# B156A.net
KiCad netlist of a schematic drawn in EAGLE
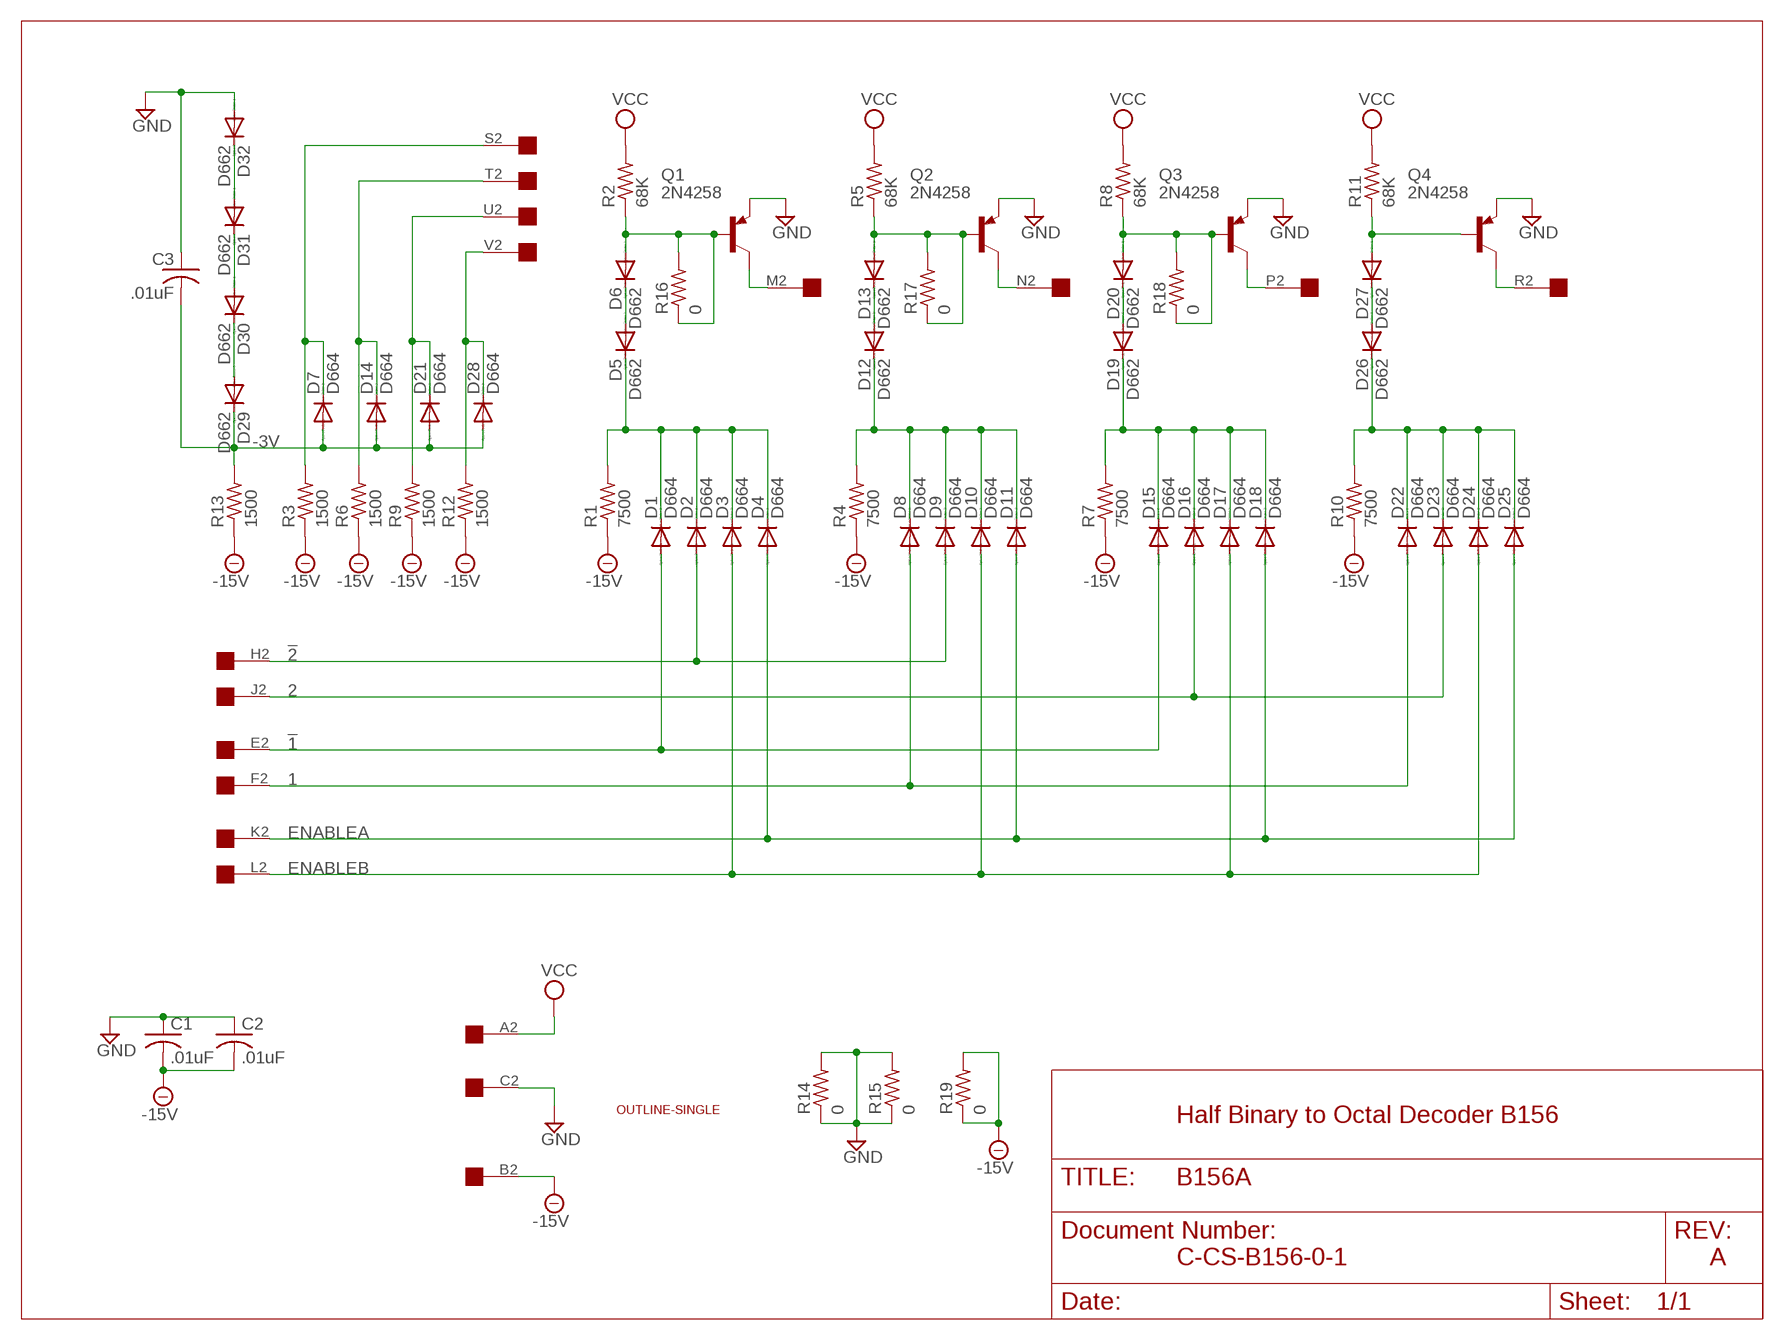
[diagram p0: schematic, sheet 1]

(export (version "E")
  (design (tool "Eeschema 10.0.6"))
  (components
    (comp (ref "C1")
      (value ".01uF")
      (footprint "eagle-import:C063-025X075")
      (libsource (lib "eagle-import") (part "C-US"))
    )
    (comp (ref "C2")
      (value ".01uF")
      (footprint "eagle-import:C063-025X075")
      (libsource (lib "eagle-import") (part "C-US"))
    )
    (comp (ref "C3")
      (value ".01uF")
      (footprint "eagle-import:C063-025X075")
      (libsource (lib "eagle-import") (part "C-US"))
    )
    (comp (ref "D1")
      (value "D664")
      (footprint "eagle-import:DO35-10")
      (libsource (lib "eagle-import") (part "DIODE-DO35-10"))
    )
    (comp (ref "D2")
      (value "D664")
      (footprint "eagle-import:DO35-10")
      (libsource (lib "eagle-import") (part "DIODE-DO35-10"))
    )
    (comp (ref "D3")
      (value "D664")
      (footprint "eagle-import:DO35-10")
      (libsource (lib "eagle-import") (part "DIODE-DO35-10"))
    )
    (comp (ref "D4")
      (value "D664")
      (footprint "eagle-import:DO35-10")
      (libsource (lib "eagle-import") (part "DIODE-DO35-10"))
    )
    (comp (ref "D5")
      (value "D662")
      (footprint "eagle-import:DO35-10")
      (libsource (lib "eagle-import") (part "DIODE-DO35-10"))
    )
    (comp (ref "D6")
      (value "D662")
      (footprint "eagle-import:DO35-10")
      (libsource (lib "eagle-import") (part "DIODE-DO35-10"))
    )
    (comp (ref "D7")
      (value "D664")
      (footprint "eagle-import:DO35-10")
      (libsource (lib "eagle-import") (part "DIODE-DO35-10"))
    )
    (comp (ref "D8")
      (value "D664")
      (footprint "eagle-import:DO35-10")
      (libsource (lib "eagle-import") (part "DIODE-DO35-10"))
    )
    (comp (ref "D9")
      (value "D664")
      (footprint "eagle-import:DO35-10")
      (libsource (lib "eagle-import") (part "DIODE-DO35-10"))
    )
    (comp (ref "D10")
      (value "D664")
      (footprint "eagle-import:DO35-10")
      (libsource (lib "eagle-import") (part "DIODE-DO35-10"))
    )
    (comp (ref "D11")
      (value "D664")
      (footprint "eagle-import:DO35-10")
      (libsource (lib "eagle-import") (part "DIODE-DO35-10"))
    )
    (comp (ref "D12")
      (value "D662")
      (footprint "eagle-import:DO35-10")
      (libsource (lib "eagle-import") (part "DIODE-DO35-10"))
    )
    (comp (ref "D13")
      (value "D662")
      (footprint "eagle-import:DO35-10")
      (libsource (lib "eagle-import") (part "DIODE-DO35-10"))
    )
    (comp (ref "D14")
      (value "D664")
      (footprint "eagle-import:DO35-10")
      (libsource (lib "eagle-import") (part "DIODE-DO35-10"))
    )
    (comp (ref "D15")
      (value "D664")
      (footprint "eagle-import:DO35-10")
      (libsource (lib "eagle-import") (part "DIODE-DO35-10"))
    )
    (comp (ref "D16")
      (value "D664")
      (footprint "eagle-import:DO35-10")
      (libsource (lib "eagle-import") (part "DIODE-DO35-10"))
    )
    (comp (ref "D17")
      (value "D664")
      (footprint "eagle-import:DO35-10")
      (libsource (lib "eagle-import") (part "DIODE-DO35-10"))
    )
    (comp (ref "D18")
      (value "D664")
      (footprint "eagle-import:DO35-10")
      (libsource (lib "eagle-import") (part "DIODE-DO35-10"))
    )
    (comp (ref "D19")
      (value "D662")
      (footprint "eagle-import:DO35-10")
      (libsource (lib "eagle-import") (part "DIODE-DO35-10"))
    )
    (comp (ref "D20")
      (value "D662")
      (footprint "eagle-import:DO35-10")
      (libsource (lib "eagle-import") (part "DIODE-DO35-10"))
    )
    (comp (ref "D21")
      (value "D664")
      (footprint "eagle-import:DO35-10")
      (libsource (lib "eagle-import") (part "DIODE-DO35-10"))
    )
    (comp (ref "D22")
      (value "D664")
      (footprint "eagle-import:DO35-10")
      (libsource (lib "eagle-import") (part "DIODE-DO35-10"))
    )
    (comp (ref "D23")
      (value "D664")
      (footprint "eagle-import:DO35-10")
      (libsource (lib "eagle-import") (part "DIODE-DO35-10"))
    )
    (comp (ref "D24")
      (value "D664")
      (footprint "eagle-import:DO35-10")
      (libsource (lib "eagle-import") (part "DIODE-DO35-10"))
    )
    (comp (ref "D25")
      (value "D664")
      (footprint "eagle-import:DO35-10")
      (libsource (lib "eagle-import") (part "DIODE-DO35-10"))
    )
    (comp (ref "D26")
      (value "D662")
      (footprint "eagle-import:DO35-10")
      (libsource (lib "eagle-import") (part "DIODE-DO35-10"))
    )
    (comp (ref "D27")
      (value "D662")
      (footprint "eagle-import:DO35-10")
      (libsource (lib "eagle-import") (part "DIODE-DO35-10"))
    )
    (comp (ref "D28")
      (value "D664")
      (footprint "eagle-import:DO35-10")
      (libsource (lib "eagle-import") (part "DIODE-DO35-10"))
    )
    (comp (ref "D29")
      (value "D662")
      (footprint "eagle-import:DO35-10")
      (libsource (lib "eagle-import") (part "DIODE-DO35-10"))
    )
    (comp (ref "D30")
      (value "D662")
      (footprint "eagle-import:DO35-10")
      (libsource (lib "eagle-import") (part "DIODE-DO35-10"))
    )
    (comp (ref "D31")
      (value "D662")
      (footprint "eagle-import:DO35-10")
      (libsource (lib "eagle-import") (part "DIODE-DO35-10"))
    )
    (comp (ref "D32")
      (value "D662")
      (footprint "eagle-import:DO35-10")
      (libsource (lib "eagle-import") (part "DIODE-DO35-10"))
    )
    (comp (ref "Q1")
      (value "2N4258")
      (footprint "eagle-import:TO5")
      (libsource (lib "eagle-import") (part "-PNP-TO5"))
    )
    (comp (ref "Q2")
      (value "2N4258")
      (footprint "eagle-import:TO5")
      (libsource (lib "eagle-import") (part "-PNP-TO5"))
    )
    (comp (ref "Q3")
      (value "2N4258")
      (footprint "eagle-import:TO5")
      (libsource (lib "eagle-import") (part "-PNP-TO5"))
    )
    (comp (ref "Q4")
      (value "2N4258")
      (footprint "eagle-import:TO5")
      (libsource (lib "eagle-import") (part "-PNP-TO5"))
    )
    (comp (ref "R1")
      (value "7500")
      (footprint "eagle-import:0207_10")
      (libsource (lib "eagle-import") (part "R-US_0207/10"))
    )
    (comp (ref "R2")
      (value "68K")
      (footprint "eagle-import:0207_10")
      (libsource (lib "eagle-import") (part "R-US_0207/10"))
    )
    (comp (ref "R3")
      (value "1500")
      (footprint "eagle-import:0207_10")
      (libsource (lib "eagle-import") (part "R-US_0207/10"))
    )
    (comp (ref "R4")
      (value "7500")
      (footprint "eagle-import:0207_10")
      (libsource (lib "eagle-import") (part "R-US_0207/10"))
    )
    (comp (ref "R5")
      (value "68K")
      (footprint "eagle-import:0207_10")
      (libsource (lib "eagle-import") (part "R-US_0207/10"))
    )
    (comp (ref "R6")
      (value "1500")
      (footprint "eagle-import:0207_10")
      (libsource (lib "eagle-import") (part "R-US_0207/10"))
    )
    (comp (ref "R7")
      (value "7500")
      (footprint "eagle-import:0207_10")
      (libsource (lib "eagle-import") (part "R-US_0207/10"))
    )
    (comp (ref "R8")
      (value "68K")
      (footprint "eagle-import:0207_10")
      (libsource (lib "eagle-import") (part "R-US_0207/10"))
    )
    (comp (ref "R9")
      (value "1500")
      (footprint "eagle-import:0207_10")
      (libsource (lib "eagle-import") (part "R-US_0207/10"))
    )
    (comp (ref "R10")
      (value "7500")
      (footprint "eagle-import:0207_10")
      (libsource (lib "eagle-import") (part "R-US_0207/10"))
    )
    (comp (ref "R11")
      (value "68K")
      (footprint "eagle-import:0207_10")
      (libsource (lib "eagle-import") (part "R-US_0207/10"))
    )
    (comp (ref "R12")
      (value "1500")
      (footprint "eagle-import:0207_10")
      (libsource (lib "eagle-import") (part "R-US_0207/10"))
    )
    (comp (ref "R13")
      (value "1500")
      (footprint "eagle-import:0207_10")
      (libsource (lib "eagle-import") (part "R-US_0207/10"))
    )
    (comp (ref "R14")
      (value "0")
      (footprint "eagle-import:0207_10")
      (libsource (lib "eagle-import") (part "R-US_0207/10"))
    )
    (comp (ref "R15")
      (value "0")
      (footprint "eagle-import:0207_10")
      (libsource (lib "eagle-import") (part "R-US_0207/10"))
    )
    (comp (ref "R16")
      (value "0")
      (footprint "eagle-import:0207_10")
      (libsource (lib "eagle-import") (part "R-US_0207/10"))
    )
    (comp (ref "R17")
      (value "0")
      (footprint "eagle-import:0207_10")
      (libsource (lib "eagle-import") (part "R-US_0207/10"))
    )
    (comp (ref "R18")
      (value "0")
      (footprint "eagle-import:0207_10")
      (libsource (lib "eagle-import") (part "R-US_0207/10"))
    )
    (comp (ref "R19")
      (value "0")
      (footprint "eagle-import:0207_10")
      (libsource (lib "eagle-import") (part "R-US_0207/10"))
    )
    (comp (ref "U$1")
      (value "OUTLINE-SINGLE")
      (footprint "eagle-import:SINGLE")
      (libsource (lib "eagle-import") (part "OUTLINE-SINGLE"))
    )
    (comp (ref "U$2")
      (value "EDGE-1")
      (footprint "eagle-import:EDGE-CON1")
      (libsource (lib "eagle-import") (part "EDGE-1"))
    )
  )
  (nets
    (net (code "1") (name "-15V") (class "Default")
      (node (ref "C1") (pin "2") (pinfunction "2_2") (pintype "passive"))
      (node (ref "C2") (pin "2") (pinfunction "2_2") (pintype "passive"))
      (node (ref "R1") (pin "1") (pinfunction "1_1") (pintype "passive"))
      (node (ref "R10") (pin "1") (pinfunction "1_1") (pintype "passive"))
      (node (ref "R12") (pin "1") (pinfunction "1_1") (pintype "passive"))
      (node (ref "R13") (pin "1") (pinfunction "1_1") (pintype "passive"))
      (node (ref "R19") (pin "1") (pinfunction "1_1") (pintype "passive"))
      (node (ref "R19") (pin "2") (pinfunction "2_2") (pintype "passive"))
      (node (ref "R3") (pin "1") (pinfunction "1_1") (pintype "passive"))
      (node (ref "R4") (pin "1") (pinfunction "1_1") (pintype "passive"))
      (node (ref "R6") (pin "1") (pinfunction "1_1") (pintype "passive"))
      (node (ref "R7") (pin "1") (pinfunction "1_1") (pintype "passive"))
      (node (ref "R9") (pin "1") (pinfunction "1_1") (pintype "passive"))
      (node (ref "U$2") (pin "B2") (pinfunction "1_B2") (pintype "bidirectional"))
    )
    (net (code "2") (name "/-3V") (class "Default")
      (node (ref "C3") (pin "2") (pinfunction "2_2") (pintype "passive"))
      (node (ref "D14") (pin "A") (pinfunction "A_A") (pintype "passive"))
      (node (ref "D21") (pin "A") (pinfunction "A_A") (pintype "passive"))
      (node (ref "D28") (pin "A") (pinfunction "A_A") (pintype "passive"))
      (node (ref "D29") (pin "C") (pinfunction "C_C") (pintype "passive"))
      (node (ref "D7") (pin "A") (pinfunction "A_A") (pintype "passive"))
      (node (ref "R13") (pin "2") (pinfunction "2_2") (pintype "passive"))
    )
    (net (code "3") (name "/1") (class "Default")
      (node (ref "D22") (pin "A") (pinfunction "A_A") (pintype "passive"))
      (node (ref "D8") (pin "A") (pinfunction "A_A") (pintype "passive"))
      (node (ref "U$2") (pin "F2") (pinfunction "1_F2") (pintype "bidirectional"))
    )
    (net (code "4") (name "/2") (class "Default")
      (node (ref "D16") (pin "A") (pinfunction "A_A") (pintype "passive"))
      (node (ref "D23") (pin "A") (pinfunction "A_A") (pintype "passive"))
      (node (ref "U$2") (pin "J2") (pinfunction "1_J2") (pintype "bidirectional"))
    )
    (net (code "5") (name "/ENABLEA") (class "Default")
      (node (ref "D11") (pin "A") (pinfunction "A_A") (pintype "passive"))
      (node (ref "D18") (pin "A") (pinfunction "A_A") (pintype "passive"))
      (node (ref "D25") (pin "A") (pinfunction "A_A") (pintype "passive"))
      (node (ref "D4") (pin "A") (pinfunction "A_A") (pintype "passive"))
      (node (ref "U$2") (pin "K2") (pinfunction "1_K2") (pintype "bidirectional"))
    )
    (net (code "6") (name "/ENABLEB") (class "Default")
      (node (ref "D10") (pin "A") (pinfunction "A_A") (pintype "passive"))
      (node (ref "D17") (pin "A") (pinfunction "A_A") (pintype "passive"))
      (node (ref "D24") (pin "A") (pinfunction "A_A") (pintype "passive"))
      (node (ref "D3") (pin "A") (pinfunction "A_A") (pintype "passive"))
      (node (ref "U$2") (pin "L2") (pinfunction "1_L2") (pintype "bidirectional"))
    )
    (net (code "7") (name "/~{1}") (class "Default")
      (node (ref "D1") (pin "A") (pinfunction "A_A") (pintype "passive"))
      (node (ref "D15") (pin "A") (pinfunction "A_A") (pintype "passive"))
      (node (ref "U$2") (pin "E2") (pinfunction "1_E2") (pintype "bidirectional"))
    )
    (net (code "8") (name "/~{2}") (class "Default")
      (node (ref "D2") (pin "A") (pinfunction "A_A") (pintype "passive"))
      (node (ref "D9") (pin "A") (pinfunction "A_A") (pintype "passive"))
      (node (ref "U$2") (pin "H2") (pinfunction "1_H2") (pintype "bidirectional"))
    )
    (net (code "9") (name "GND") (class "Default")
      (node (ref "C1") (pin "1") (pinfunction "1_1") (pintype "passive"))
      (node (ref "C2") (pin "1") (pinfunction "1_1") (pintype "passive"))
      (node (ref "C3") (pin "1") (pinfunction "1_1") (pintype "passive"))
      (node (ref "D32") (pin "A") (pinfunction "A_A") (pintype "passive"))
      (node (ref "Q1") (pin "1") (pinfunction "E_1") (pintype "passive"))
      (node (ref "Q2") (pin "1") (pinfunction "E_1") (pintype "passive"))
      (node (ref "Q3") (pin "1") (pinfunction "E_1") (pintype "passive"))
      (node (ref "Q4") (pin "1") (pinfunction "E_1") (pintype "passive"))
      (node (ref "R14") (pin "1") (pinfunction "1_1") (pintype "passive"))
      (node (ref "R14") (pin "2") (pinfunction "2_2") (pintype "passive"))
      (node (ref "R15") (pin "1") (pinfunction "1_1") (pintype "passive"))
      (node (ref "R15") (pin "2") (pinfunction "2_2") (pintype "passive"))
      (node (ref "U$2") (pin "C2") (pinfunction "1_C2") (pintype "bidirectional"))
    )
    (net (code "10") (name "Net-(D1-PadC)") (class "Default")
      (node (ref "D1") (pin "C") (pinfunction "C_C") (pintype "passive"))
      (node (ref "D2") (pin "C") (pinfunction "C_C") (pintype "passive"))
      (node (ref "D3") (pin "C") (pinfunction "C_C") (pintype "passive"))
      (node (ref "D4") (pin "C") (pinfunction "C_C") (pintype "passive"))
      (node (ref "D5") (pin "C") (pinfunction "C_C") (pintype "passive"))
      (node (ref "R1") (pin "2") (pinfunction "2_2") (pintype "passive"))
    )
    (net (code "11") (name "Net-(D5-PadA)") (class "Default")
      (node (ref "D5") (pin "A") (pinfunction "A_A") (pintype "passive"))
      (node (ref "D6") (pin "C") (pinfunction "C_C") (pintype "passive"))
    )
    (net (code "12") (name "Net-(D10-PadC)") (class "Default")
      (node (ref "D10") (pin "C") (pinfunction "C_C") (pintype "passive"))
      (node (ref "D11") (pin "C") (pinfunction "C_C") (pintype "passive"))
      (node (ref "D12") (pin "C") (pinfunction "C_C") (pintype "passive"))
      (node (ref "D8") (pin "C") (pinfunction "C_C") (pintype "passive"))
      (node (ref "D9") (pin "C") (pinfunction "C_C") (pintype "passive"))
      (node (ref "R4") (pin "2") (pinfunction "2_2") (pintype "passive"))
    )
    (net (code "13") (name "Net-(D12-PadA)") (class "Default")
      (node (ref "D12") (pin "A") (pinfunction "A_A") (pintype "passive"))
      (node (ref "D13") (pin "C") (pinfunction "C_C") (pintype "passive"))
    )
    (net (code "14") (name "Net-(D15-PadC)") (class "Default")
      (node (ref "D15") (pin "C") (pinfunction "C_C") (pintype "passive"))
      (node (ref "D16") (pin "C") (pinfunction "C_C") (pintype "passive"))
      (node (ref "D17") (pin "C") (pinfunction "C_C") (pintype "passive"))
      (node (ref "D18") (pin "C") (pinfunction "C_C") (pintype "passive"))
      (node (ref "D19") (pin "C") (pinfunction "C_C") (pintype "passive"))
      (node (ref "R7") (pin "2") (pinfunction "2_2") (pintype "passive"))
    )
    (net (code "15") (name "Net-(D19-PadA)") (class "Default")
      (node (ref "D19") (pin "A") (pinfunction "A_A") (pintype "passive"))
      (node (ref "D20") (pin "C") (pinfunction "C_C") (pintype "passive"))
    )
    (net (code "16") (name "Net-(D22-PadC)") (class "Default")
      (node (ref "D22") (pin "C") (pinfunction "C_C") (pintype "passive"))
      (node (ref "D23") (pin "C") (pinfunction "C_C") (pintype "passive"))
      (node (ref "D24") (pin "C") (pinfunction "C_C") (pintype "passive"))
      (node (ref "D25") (pin "C") (pinfunction "C_C") (pintype "passive"))
      (node (ref "D26") (pin "C") (pinfunction "C_C") (pintype "passive"))
      (node (ref "R10") (pin "2") (pinfunction "2_2") (pintype "passive"))
    )
    (net (code "17") (name "Net-(D26-PadA)") (class "Default")
      (node (ref "D26") (pin "A") (pinfunction "A_A") (pintype "passive"))
      (node (ref "D27") (pin "C") (pinfunction "C_C") (pintype "passive"))
    )
    (net (code "18") (name "Net-(D29-PadA)") (class "Default")
      (node (ref "D29") (pin "A") (pinfunction "A_A") (pintype "passive"))
      (node (ref "D30") (pin "C") (pinfunction "C_C") (pintype "passive"))
    )
    (net (code "19") (name "Net-(D30-PadA)") (class "Default")
      (node (ref "D30") (pin "A") (pinfunction "A_A") (pintype "passive"))
      (node (ref "D31") (pin "C") (pinfunction "C_C") (pintype "passive"))
    )
    (net (code "20") (name "Net-(D31-PadA)") (class "Default")
      (node (ref "D31") (pin "A") (pinfunction "A_A") (pintype "passive"))
      (node (ref "D32") (pin "C") (pinfunction "C_C") (pintype "passive"))
    )
    (net (code "21") (name "Net-(Q1-B)") (class "Default")
      (node (ref "D6") (pin "A") (pinfunction "A_A") (pintype "passive"))
      (node (ref "Q1") (pin "2") (pinfunction "B_2") (pintype "passive"))
      (node (ref "R16") (pin "1") (pinfunction "1_1") (pintype "passive"))
      (node (ref "R16") (pin "2") (pinfunction "2_2") (pintype "passive"))
      (node (ref "R2") (pin "1") (pinfunction "1_1") (pintype "passive"))
    )
    (net (code "22") (name "Net-(Q1-C)") (class "Default")
      (node (ref "Q1") (pin "3") (pinfunction "C_3") (pintype "passive"))
      (node (ref "U$2") (pin "M2") (pinfunction "1_M2") (pintype "bidirectional"))
    )
    (net (code "23") (name "Net-(Q2-B)") (class "Default")
      (node (ref "D13") (pin "A") (pinfunction "A_A") (pintype "passive"))
      (node (ref "Q2") (pin "2") (pinfunction "B_2") (pintype "passive"))
      (node (ref "R17") (pin "1") (pinfunction "1_1") (pintype "passive"))
      (node (ref "R17") (pin "2") (pinfunction "2_2") (pintype "passive"))
      (node (ref "R5") (pin "1") (pinfunction "1_1") (pintype "passive"))
    )
    (net (code "24") (name "Net-(Q2-C)") (class "Default")
      (node (ref "Q2") (pin "3") (pinfunction "C_3") (pintype "passive"))
      (node (ref "U$2") (pin "N2") (pinfunction "1_N2") (pintype "bidirectional"))
    )
    (net (code "25") (name "Net-(Q3-B)") (class "Default")
      (node (ref "D20") (pin "A") (pinfunction "A_A") (pintype "passive"))
      (node (ref "Q3") (pin "2") (pinfunction "B_2") (pintype "passive"))
      (node (ref "R18") (pin "1") (pinfunction "1_1") (pintype "passive"))
      (node (ref "R18") (pin "2") (pinfunction "2_2") (pintype "passive"))
      (node (ref "R8") (pin "1") (pinfunction "1_1") (pintype "passive"))
    )
    (net (code "26") (name "Net-(Q3-C)") (class "Default")
      (node (ref "Q3") (pin "3") (pinfunction "C_3") (pintype "passive"))
      (node (ref "U$2") (pin "P2") (pinfunction "1_P2") (pintype "bidirectional"))
    )
    (net (code "27") (name "Net-(Q4-B)") (class "Default")
      (node (ref "D27") (pin "A") (pinfunction "A_A") (pintype "passive"))
      (node (ref "Q4") (pin "2") (pinfunction "B_2") (pintype "passive"))
      (node (ref "R11") (pin "1") (pinfunction "1_1") (pintype "passive"))
    )
    (net (code "28") (name "Net-(Q4-C)") (class "Default")
      (node (ref "Q4") (pin "3") (pinfunction "C_3") (pintype "passive"))
      (node (ref "U$2") (pin "R2") (pinfunction "1_R2") (pintype "bidirectional"))
    )
    (net (code "29") (name "Net-(U$2O-1)") (class "Default")
      (node (ref "D7") (pin "C") (pinfunction "C_C") (pintype "passive"))
      (node (ref "R3") (pin "2") (pinfunction "2_2") (pintype "passive"))
      (node (ref "U$2") (pin "S2") (pinfunction "1_S2") (pintype "bidirectional"))
    )
    (net (code "30") (name "Net-(U$2P-1)") (class "Default")
      (node (ref "D14") (pin "C") (pinfunction "C_C") (pintype "passive"))
      (node (ref "R6") (pin "2") (pinfunction "2_2") (pintype "passive"))
      (node (ref "U$2") (pin "T2") (pinfunction "1_T2") (pintype "bidirectional"))
    )
    (net (code "31") (name "Net-(U$2Q-1)") (class "Default")
      (node (ref "D21") (pin "C") (pinfunction "C_C") (pintype "passive"))
      (node (ref "R9") (pin "2") (pinfunction "2_2") (pintype "passive"))
      (node (ref "U$2") (pin "U2") (pinfunction "1_U2") (pintype "bidirectional"))
    )
    (net (code "32") (name "Net-(U$2R-1)") (class "Default")
      (node (ref "D28") (pin "C") (pinfunction "C_C") (pintype "passive"))
      (node (ref "R12") (pin "2") (pinfunction "2_2") (pintype "passive"))
      (node (ref "U$2") (pin "V2") (pinfunction "1_V2") (pintype "bidirectional"))
    )
    (net (code "33") (name "VCC") (class "Default")
      (node (ref "R11") (pin "2") (pinfunction "2_2") (pintype "passive"))
      (node (ref "R2") (pin "2") (pinfunction "2_2") (pintype "passive"))
      (node (ref "R5") (pin "2") (pinfunction "2_2") (pintype "passive"))
      (node (ref "R8") (pin "2") (pinfunction "2_2") (pintype "passive"))
      (node (ref "U$2") (pin "A2") (pinfunction "1_A2") (pintype "bidirectional"))
    )
  )
)
